# rcio_v2.net
KiCad netlist of a schematic drawn in EAGLE
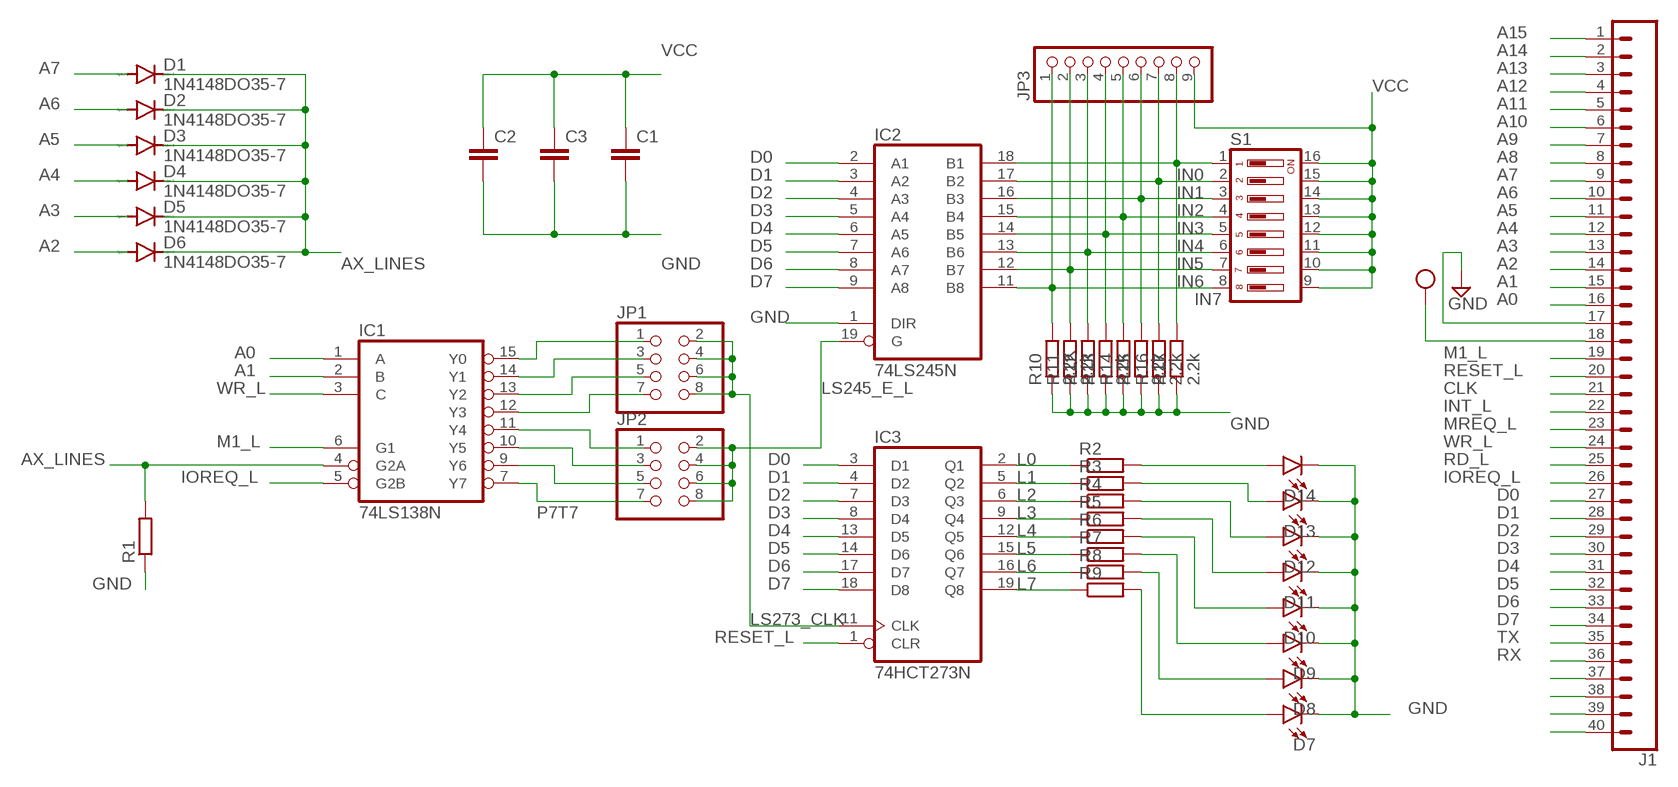
[diagram p0: schematic, sheet 1]

(export (version "E")
  (design (tool "Eeschema 10.0.6"))
  (components
    (comp (ref "C1")
      (value "C-EU050-025X075")
      (footprint "eagle-import:C050-025X075")
      (libsource (lib "eagle-import") (part "rcl_334_C-EU050-025X075"))
    )
    (comp (ref "C2")
      (value "C-EU050-025X075")
      (footprint "eagle-import:C050-025X075")
      (libsource (lib "eagle-import") (part "C-EU050-025X075"))
    )
    (comp (ref "C3")
      (value "C-EU050-025X075")
      (footprint "eagle-import:C050-025X075")
      (libsource (lib "eagle-import") (part "C-EU050-025X075"))
    )
    (comp (ref "D1")
      (value "1N4148DO35-7")
      (footprint "eagle-import:DO35-7")
      (libsource (lib "eagle-import") (part "1N4148DO35-7"))
    )
    (comp (ref "D2")
      (value "1N4148DO35-7")
      (footprint "eagle-import:DO35-7")
      (libsource (lib "eagle-import") (part "1N4148DO35-7"))
    )
    (comp (ref "D3")
      (value "1N4148DO35-7")
      (footprint "eagle-import:DO35-7")
      (libsource (lib "eagle-import") (part "1N4148DO35-7"))
    )
    (comp (ref "D4")
      (value "1N4148DO35-7")
      (footprint "eagle-import:DO35-7")
      (libsource (lib "eagle-import") (part "1N4148DO35-7"))
    )
    (comp (ref "D5")
      (value "1N4148DO35-7")
      (footprint "eagle-import:DO35-7")
      (libsource (lib "eagle-import") (part "1N4148DO35-7"))
    )
    (comp (ref "D6")
      (value "1N4148DO35-7")
      (footprint "eagle-import:DO35-7")
      (libsource (lib "eagle-import") (part "1N4148DO35-7"))
    )
    (comp (ref "D7")
      (value "LED3MM")
      (footprint "eagle-import:LED_3MM")
      (libsource (lib "eagle-import") (part "LED3MM"))
    )
    (comp (ref "D8")
      (value "LED3MM")
      (footprint "eagle-import:LED_3MM")
      (libsource (lib "eagle-import") (part "LED3MM"))
    )
    (comp (ref "D9")
      (value "LED3MM")
      (footprint "eagle-import:LED_3MM")
      (libsource (lib "eagle-import") (part "LED3MM"))
    )
    (comp (ref "D10")
      (value "LED3MM")
      (footprint "eagle-import:LED_3MM")
      (libsource (lib "eagle-import") (part "LED3MM"))
    )
    (comp (ref "D11")
      (value "LED3MM")
      (footprint "eagle-import:LED_3MM")
      (libsource (lib "eagle-import") (part "LED3MM"))
    )
    (comp (ref "D12")
      (value "LED3MM")
      (footprint "eagle-import:LED_3MM")
      (libsource (lib "eagle-import") (part "LED3MM"))
    )
    (comp (ref "D13")
      (value "LED3MM")
      (footprint "eagle-import:LED_3MM")
      (libsource (lib "eagle-import") (part "LED3MM"))
    )
    (comp (ref "D14")
      (value "LED3MM")
      (footprint "eagle-import:LED_3MM")
      (libsource (lib "eagle-import") (part "LED3MM"))
    )
    (comp (ref "IC1")
      (value "74LS138N")
      (footprint "eagle-import:DIL16")
      (libsource (lib "eagle-import") (part "74138NLS"))
    )
    (comp (ref "IC2")
      (value "74LS245N")
      (footprint "eagle-import:DIL20")
      (libsource (lib "eagle-import") (part "74245NLS"))
    )
    (comp (ref "IC3")
      (value "74HCT273N")
      (footprint "eagle-import:DIL20")
      (libsource (lib "eagle-import") (part "74273NHCT"))
    )
    (comp (ref "J1")
      (value "CONN_40OFFSET")
      (footprint "eagle-import:1X40_OFFSET")
      (libsource (lib "eagle-import") (part "CONN_40OFFSET"))
    )
    (comp (ref "JP1")
      (value "PINHD-2X4")
      (footprint "eagle-import:2X04")
      (libsource (lib "eagle-import") (part "PINHD-2X4"))
    )
    (comp (ref "JP2")
      (value "PINHD-2X4")
      (footprint "eagle-import:2X04")
      (libsource (lib "eagle-import") (part "PINHD-2X4"))
    )
    (comp (ref "JP3")
      (value "PINHD-1X9")
      (footprint "eagle-import:1X09")
      (libsource (lib "eagle-import") (part "PINHD-1X9"))
    )
    (comp (ref "R1")
      (value "R-EU_0204/7")
      (footprint "eagle-import:0204_7")
      (libsource (lib "eagle-import") (part "R-EU_0204/7"))
    )
    (comp (ref "R2")
      (value "R-EU_0204/7")
      (footprint "eagle-import:0204_7")
      (libsource (lib "eagle-import") (part "R-EU_0204/7"))
    )
    (comp (ref "R3")
      (value "R-EU_0204/7")
      (footprint "eagle-import:0204_7")
      (libsource (lib "eagle-import") (part "R-EU_0204/7"))
    )
    (comp (ref "R4")
      (value "R-EU_0204/7")
      (footprint "eagle-import:0204_7")
      (libsource (lib "eagle-import") (part "R-EU_0204/7"))
    )
    (comp (ref "R5")
      (value "R-EU_0204/7")
      (footprint "eagle-import:0204_7")
      (libsource (lib "eagle-import") (part "R-EU_0204/7"))
    )
    (comp (ref "R6")
      (value "R-EU_0204/7")
      (footprint "eagle-import:0204_7")
      (libsource (lib "eagle-import") (part "R-EU_0204/7"))
    )
    (comp (ref "R7")
      (value "R-EU_0204/7")
      (footprint "eagle-import:0204_7")
      (libsource (lib "eagle-import") (part "R-EU_0204/7"))
    )
    (comp (ref "R8")
      (value "R-EU_0204/7")
      (footprint "eagle-import:0204_7")
      (libsource (lib "eagle-import") (part "R-EU_0204/7"))
    )
    (comp (ref "R9")
      (value "R-EU_0204/7")
      (footprint "eagle-import:0204_7")
      (libsource (lib "eagle-import") (part "R-EU_0204/7"))
    )
    (comp (ref "R10")
      (value "2.2K")
      (footprint "eagle-import:0204_7")
      (libsource (lib "eagle-import") (part "R-EU_0204/7"))
    )
    (comp (ref "R11")
      (value "2.2k")
      (footprint "eagle-import:0204_7")
      (libsource (lib "eagle-import") (part "R-EU_0204/7"))
    )
    (comp (ref "R12")
      (value "R-EU_0204/7")
      (footprint "eagle-import:0204_7")
      (libsource (lib "eagle-import") (part "R-EU_0204/7"))
    )
    (comp (ref "R13")
      (value "2.2k")
      (footprint "eagle-import:0204_7")
      (libsource (lib "eagle-import") (part "R-EU_0204/7"))
    )
    (comp (ref "R14")
      (value "R-EU_0204/7")
      (footprint "eagle-import:0204_7")
      (libsource (lib "eagle-import") (part "R-EU_0204/7"))
    )
    (comp (ref "R15")
      (value "2.2k")
      (footprint "eagle-import:0204_7")
      (libsource (lib "eagle-import") (part "R-EU_0204/7"))
    )
    (comp (ref "R16")
      (value "2.2k")
      (footprint "eagle-import:0204_7")
      (libsource (lib "eagle-import") (part "R-EU_0204/7"))
    )
    (comp (ref "R17")
      (value "2.2k")
      (footprint "eagle-import:0204_7")
      (libsource (lib "eagle-import") (part "R-EU_0204/7"))
    )
    (comp (ref "S1")
      (value "DP08")
      (footprint "eagle-import:DP-08")
      (libsource (lib "eagle-import") (part "DP08"))
    )
  )
  (nets
    (net (code "1") (name "/A0") (class "Default")
      (node (ref "IC1") (pin "1") (pinfunction "A_1") (pintype "input"))
      (node (ref "J1") (pin "16") (pinfunction "16_16") (pintype "passive"))
    )
    (net (code "2") (name "/A1") (class "Default")
      (node (ref "IC1") (pin "2") (pinfunction "B_2") (pintype "input"))
      (node (ref "J1") (pin "15") (pinfunction "15_15") (pintype "passive"))
    )
    (net (code "3") (name "/A2") (class "Default")
      (node (ref "D6") (pin "A") (pinfunction "A_A") (pintype "passive"))
      (node (ref "J1") (pin "14") (pinfunction "14_14") (pintype "passive"))
    )
    (net (code "4") (name "/A3") (class "Default")
      (node (ref "D5") (pin "A") (pinfunction "A_A") (pintype "passive"))
      (node (ref "J1") (pin "13") (pinfunction "13_13") (pintype "passive"))
    )
    (net (code "5") (name "/A4") (class "Default")
      (node (ref "D4") (pin "A") (pinfunction "A_A") (pintype "passive"))
      (node (ref "J1") (pin "12") (pinfunction "12_12") (pintype "passive"))
    )
    (net (code "6") (name "/A5") (class "Default")
      (node (ref "D3") (pin "A") (pinfunction "A_A") (pintype "passive"))
      (node (ref "J1") (pin "11") (pinfunction "11_11") (pintype "passive"))
    )
    (net (code "7") (name "/A6") (class "Default")
      (node (ref "D2") (pin "A") (pinfunction "A_A") (pintype "passive"))
      (node (ref "J1") (pin "10") (pinfunction "10_10") (pintype "passive"))
    )
    (net (code "8") (name "/A7") (class "Default")
      (node (ref "D1") (pin "A") (pinfunction "A_A") (pintype "passive"))
      (node (ref "J1") (pin "9") (pinfunction "9_9") (pintype "passive"))
    )
    (net (code "9") (name "/A8") (class "Default")
      (node (ref "J1") (pin "8") (pinfunction "8_8") (pintype "passive"))
    )
    (net (code "10") (name "/A9") (class "Default")
      (node (ref "J1") (pin "7") (pinfunction "7_7") (pintype "passive"))
    )
    (net (code "11") (name "/A10") (class "Default")
      (node (ref "J1") (pin "6") (pinfunction "6_6") (pintype "passive"))
    )
    (net (code "12") (name "/A11") (class "Default")
      (node (ref "J1") (pin "5") (pinfunction "5_5") (pintype "passive"))
    )
    (net (code "13") (name "/A12") (class "Default")
      (node (ref "J1") (pin "4") (pinfunction "4_4") (pintype "passive"))
    )
    (net (code "14") (name "/A13") (class "Default")
      (node (ref "J1") (pin "3") (pinfunction "3_3") (pintype "passive"))
    )
    (net (code "15") (name "/A14") (class "Default")
      (node (ref "J1") (pin "2") (pinfunction "2_2") (pintype "passive"))
    )
    (net (code "16") (name "/A15") (class "Default")
      (node (ref "J1") (pin "1") (pinfunction "1_1") (pintype "passive"))
    )
    (net (code "17") (name "/AX_LINES") (class "Default")
      (node (ref "D1") (pin "C") (pinfunction "C_C") (pintype "passive"))
      (node (ref "D2") (pin "C") (pinfunction "C_C") (pintype "passive"))
      (node (ref "D3") (pin "C") (pinfunction "C_C") (pintype "passive"))
      (node (ref "D4") (pin "C") (pinfunction "C_C") (pintype "passive"))
      (node (ref "D5") (pin "C") (pinfunction "C_C") (pintype "passive"))
      (node (ref "D6") (pin "C") (pinfunction "C_C") (pintype "passive"))
      (node (ref "IC1") (pin "4") (pinfunction "G2A_4") (pintype "input"))
      (node (ref "R1") (pin "2") (pinfunction "2_2") (pintype "passive"))
    )
    (net (code "18") (name "/CLK") (class "Default")
      (node (ref "J1") (pin "21") (pinfunction "21_21") (pintype "passive"))
    )
    (net (code "19") (name "/D0") (class "Default")
      (node (ref "IC2") (pin "2") (pinfunction "A1_2") (pintype "bidirectional"))
      (node (ref "IC3") (pin "3") (pinfunction "D1_3") (pintype "input"))
      (node (ref "J1") (pin "27") (pinfunction "27_27") (pintype "passive"))
    )
    (net (code "20") (name "/D1") (class "Default")
      (node (ref "IC2") (pin "3") (pinfunction "A2_3") (pintype "bidirectional"))
      (node (ref "IC3") (pin "4") (pinfunction "D2_4") (pintype "input"))
      (node (ref "J1") (pin "28") (pinfunction "28_28") (pintype "passive"))
    )
    (net (code "21") (name "/D2") (class "Default")
      (node (ref "IC2") (pin "4") (pinfunction "A3_4") (pintype "bidirectional"))
      (node (ref "IC3") (pin "7") (pinfunction "D3_7") (pintype "input"))
      (node (ref "J1") (pin "29") (pinfunction "29_29") (pintype "passive"))
    )
    (net (code "22") (name "/D3") (class "Default")
      (node (ref "IC2") (pin "5") (pinfunction "A4_5") (pintype "bidirectional"))
      (node (ref "IC3") (pin "8") (pinfunction "D4_8") (pintype "input"))
      (node (ref "J1") (pin "30") (pinfunction "30_30") (pintype "passive"))
    )
    (net (code "23") (name "/D4") (class "Default")
      (node (ref "IC2") (pin "6") (pinfunction "A5_6") (pintype "bidirectional"))
      (node (ref "IC3") (pin "13") (pinfunction "D5_13") (pintype "input"))
      (node (ref "J1") (pin "31") (pinfunction "31_31") (pintype "passive"))
    )
    (net (code "24") (name "/D5") (class "Default")
      (node (ref "IC2") (pin "7") (pinfunction "A6_7") (pintype "bidirectional"))
      (node (ref "IC3") (pin "14") (pinfunction "D6_14") (pintype "input"))
      (node (ref "J1") (pin "32") (pinfunction "32_32") (pintype "passive"))
    )
    (net (code "25") (name "/D6") (class "Default")
      (node (ref "IC2") (pin "8") (pinfunction "A7_8") (pintype "bidirectional"))
      (node (ref "IC3") (pin "17") (pinfunction "D7_17") (pintype "input"))
      (node (ref "J1") (pin "33") (pinfunction "33_33") (pintype "passive"))
    )
    (net (code "26") (name "/D7") (class "Default")
      (node (ref "IC2") (pin "9") (pinfunction "A8_9") (pintype "bidirectional"))
      (node (ref "IC3") (pin "18") (pinfunction "D8_18") (pintype "input"))
      (node (ref "J1") (pin "34") (pinfunction "34_34") (pintype "passive"))
    )
    (net (code "27") (name "/IN0") (class "Default")
      (node (ref "IC2") (pin "18") (pinfunction "B1_18") (pintype "bidirectional"))
      (node (ref "JP3") (pin "8") (pinfunction "8_8") (pintype "passive"))
      (node (ref "R17") (pin "2") (pinfunction "2_2") (pintype "passive"))
      (node (ref "S1") (pin "1") (pinfunction "1_1") (pintype "passive"))
    )
    (net (code "28") (name "/IN1") (class "Default")
      (node (ref "IC2") (pin "17") (pinfunction "B2_17") (pintype "bidirectional"))
      (node (ref "JP3") (pin "7") (pinfunction "7_7") (pintype "passive"))
      (node (ref "R16") (pin "2") (pinfunction "2_2") (pintype "passive"))
      (node (ref "S1") (pin "2") (pinfunction "2_2") (pintype "passive"))
    )
    (net (code "29") (name "/IN2") (class "Default")
      (node (ref "IC2") (pin "16") (pinfunction "B3_16") (pintype "bidirectional"))
      (node (ref "JP3") (pin "6") (pinfunction "6_6") (pintype "passive"))
      (node (ref "R15") (pin "2") (pinfunction "2_2") (pintype "passive"))
      (node (ref "S1") (pin "3") (pinfunction "3_3") (pintype "passive"))
    )
    (net (code "30") (name "/IN3") (class "Default")
      (node (ref "IC2") (pin "15") (pinfunction "B4_15") (pintype "bidirectional"))
      (node (ref "JP3") (pin "5") (pinfunction "5_5") (pintype "passive"))
      (node (ref "R14") (pin "2") (pinfunction "2_2") (pintype "passive"))
      (node (ref "S1") (pin "4") (pinfunction "4_4") (pintype "passive"))
    )
    (net (code "31") (name "/IN4") (class "Default")
      (node (ref "IC2") (pin "14") (pinfunction "B5_14") (pintype "bidirectional"))
      (node (ref "JP3") (pin "4") (pinfunction "4_4") (pintype "passive"))
      (node (ref "R13") (pin "2") (pinfunction "2_2") (pintype "passive"))
      (node (ref "S1") (pin "5") (pinfunction "5_5") (pintype "passive"))
    )
    (net (code "32") (name "/IN5") (class "Default")
      (node (ref "IC2") (pin "13") (pinfunction "B6_13") (pintype "bidirectional"))
      (node (ref "JP3") (pin "3") (pinfunction "3_3") (pintype "passive"))
      (node (ref "R12") (pin "2") (pinfunction "2_2") (pintype "passive"))
      (node (ref "S1") (pin "6") (pinfunction "6_6") (pintype "passive"))
    )
    (net (code "33") (name "/IN6") (class "Default")
      (node (ref "IC2") (pin "12") (pinfunction "B7_12") (pintype "bidirectional"))
      (node (ref "JP3") (pin "2") (pinfunction "2_2") (pintype "passive"))
      (node (ref "R11") (pin "2") (pinfunction "2_2") (pintype "passive"))
      (node (ref "S1") (pin "7") (pinfunction "7_7") (pintype "passive"))
    )
    (net (code "34") (name "/IN7") (class "Default")
      (node (ref "IC2") (pin "11") (pinfunction "B8_11") (pintype "bidirectional"))
      (node (ref "JP3") (pin "1") (pinfunction "1_1") (pintype "passive"))
      (node (ref "R10") (pin "2") (pinfunction "2_2") (pintype "passive"))
      (node (ref "S1") (pin "8") (pinfunction "8_8") (pintype "passive"))
    )
    (net (code "35") (name "/INT_L") (class "Default")
      (node (ref "J1") (pin "22") (pinfunction "22_22") (pintype "passive"))
    )
    (net (code "36") (name "/IOREQ_L") (class "Default")
      (node (ref "IC1") (pin "5") (pinfunction "G2B_5") (pintype "input"))
      (node (ref "J1") (pin "26") (pinfunction "26_26") (pintype "passive"))
    )
    (net (code "37") (name "/L0") (class "Default")
      (node (ref "IC3") (pin "2") (pinfunction "Q1_2") (pintype "output"))
      (node (ref "R2") (pin "1") (pinfunction "1_1") (pintype "passive"))
    )
    (net (code "38") (name "/L1") (class "Default")
      (node (ref "IC3") (pin "5") (pinfunction "Q2_5") (pintype "output"))
      (node (ref "R3") (pin "1") (pinfunction "1_1") (pintype "passive"))
    )
    (net (code "39") (name "/L2") (class "Default")
      (node (ref "IC3") (pin "6") (pinfunction "Q3_6") (pintype "output"))
      (node (ref "R4") (pin "1") (pinfunction "1_1") (pintype "passive"))
    )
    (net (code "40") (name "/L3") (class "Default")
      (node (ref "IC3") (pin "9") (pinfunction "Q4_9") (pintype "output"))
      (node (ref "R5") (pin "1") (pinfunction "1_1") (pintype "passive"))
    )
    (net (code "41") (name "/L4") (class "Default")
      (node (ref "IC3") (pin "12") (pinfunction "Q5_12") (pintype "output"))
      (node (ref "R6") (pin "1") (pinfunction "1_1") (pintype "passive"))
    )
    (net (code "42") (name "/L5") (class "Default")
      (node (ref "IC3") (pin "15") (pinfunction "Q6_15") (pintype "output"))
      (node (ref "R7") (pin "1") (pinfunction "1_1") (pintype "passive"))
    )
    (net (code "43") (name "/L6") (class "Default")
      (node (ref "IC3") (pin "16") (pinfunction "Q7_16") (pintype "output"))
      (node (ref "R8") (pin "1") (pinfunction "1_1") (pintype "passive"))
    )
    (net (code "44") (name "/L7") (class "Default")
      (node (ref "IC3") (pin "19") (pinfunction "Q8_19") (pintype "output"))
      (node (ref "R9") (pin "1") (pinfunction "1_1") (pintype "passive"))
    )
    (net (code "45") (name "/LS245_E_L") (class "Default")
      (node (ref "IC2") (pin "19") (pinfunction "G_19") (pintype "input"))
      (node (ref "JP2") (pin "2") (pinfunction "2_2") (pintype "passive"))
      (node (ref "JP2") (pin "4") (pinfunction "4_4") (pintype "passive"))
      (node (ref "JP2") (pin "6") (pinfunction "6_6") (pintype "passive"))
      (node (ref "JP2") (pin "8") (pinfunction "8_8") (pintype "passive"))
    )
    (net (code "46") (name "/LS273_CLK") (class "Default")
      (node (ref "IC3") (pin "11") (pinfunction "CLK_11") (pintype "input"))
      (node (ref "JP1") (pin "2") (pinfunction "2_2") (pintype "passive"))
      (node (ref "JP1") (pin "4") (pinfunction "4_4") (pintype "passive"))
      (node (ref "JP1") (pin "6") (pinfunction "6_6") (pintype "passive"))
      (node (ref "JP1") (pin "8") (pinfunction "8_8") (pintype "passive"))
    )
    (net (code "47") (name "/M1_L") (class "Default")
      (node (ref "IC1") (pin "6") (pinfunction "G1_6") (pintype "input"))
      (node (ref "J1") (pin "19") (pinfunction "19_19") (pintype "passive"))
    )
    (net (code "48") (name "/MREQ_L") (class "Default")
      (node (ref "J1") (pin "23") (pinfunction "23_23") (pintype "passive"))
    )
    (net (code "49") (name "/P7T7") (class "Default")
      (node (ref "IC1") (pin "7") (pinfunction "Y7_7") (pintype "output"))
      (node (ref "JP2") (pin "7") (pinfunction "7_7") (pintype "passive"))
    )
    (net (code "50") (name "/RD_L") (class "Default")
      (node (ref "J1") (pin "25") (pinfunction "25_25") (pintype "passive"))
    )
    (net (code "51") (name "/RESET_L") (class "Default")
      (node (ref "IC3") (pin "1") (pinfunction "CLR_1") (pintype "input"))
      (node (ref "J1") (pin "20") (pinfunction "20_20") (pintype "passive"))
    )
    (net (code "52") (name "/RX") (class "Default")
      (node (ref "J1") (pin "36") (pinfunction "36_36") (pintype "passive"))
    )
    (net (code "53") (name "/TX") (class "Default")
      (node (ref "J1") (pin "35") (pinfunction "35_35") (pintype "passive"))
    )
    (net (code "54") (name "/WR_L") (class "Default")
      (node (ref "IC1") (pin "3") (pinfunction "C_3") (pintype "input"))
      (node (ref "J1") (pin "24") (pinfunction "24_24") (pintype "passive"))
    )
    (net (code "55") (name "GND") (class "Default")
      (node (ref "C1") (pin "2") (pinfunction "2_2") (pintype "passive"))
      (node (ref "C2") (pin "2") (pinfunction "2_2") (pintype "passive"))
      (node (ref "C3") (pin "2") (pinfunction "2_2") (pintype "passive"))
      (node (ref "D10") (pin "K") (pinfunction "C_K") (pintype "passive"))
      (node (ref "D11") (pin "K") (pinfunction "C_K") (pintype "passive"))
      (node (ref "D12") (pin "K") (pinfunction "C_K") (pintype "passive"))
      (node (ref "D13") (pin "K") (pinfunction "C_K") (pintype "passive"))
      (node (ref "D14") (pin "K") (pinfunction "C_K") (pintype "passive"))
      (node (ref "D7") (pin "K") (pinfunction "C_K") (pintype "passive"))
      (node (ref "D8") (pin "K") (pinfunction "C_K") (pintype "passive"))
      (node (ref "D9") (pin "K") (pinfunction "C_K") (pintype "passive"))
      (node (ref "IC2") (pin "1") (pinfunction "DIR_1") (pintype "input"))
      (node (ref "J1") (pin "17") (pinfunction "17_17") (pintype "passive"))
      (node (ref "R1") (pin "1") (pinfunction "1_1") (pintype "passive"))
      (node (ref "R10") (pin "1") (pinfunction "1_1") (pintype "passive"))
      (node (ref "R11") (pin "1") (pinfunction "1_1") (pintype "passive"))
      (node (ref "R12") (pin "1") (pinfunction "1_1") (pintype "passive"))
      (node (ref "R13") (pin "1") (pinfunction "1_1") (pintype "passive"))
      (node (ref "R14") (pin "1") (pinfunction "1_1") (pintype "passive"))
      (node (ref "R15") (pin "1") (pinfunction "1_1") (pintype "passive"))
      (node (ref "R16") (pin "1") (pinfunction "1_1") (pintype "passive"))
      (node (ref "R17") (pin "1") (pinfunction "1_1") (pintype "passive"))
    )
    (net (code "56") (name "Net-(D7-PadA)") (class "Default")
      (node (ref "D7") (pin "A") (pinfunction "A_A") (pintype "passive"))
      (node (ref "R9") (pin "2") (pinfunction "2_2") (pintype "passive"))
    )
    (net (code "57") (name "Net-(D8-PadA)") (class "Default")
      (node (ref "D8") (pin "A") (pinfunction "A_A") (pintype "passive"))
      (node (ref "R8") (pin "2") (pinfunction "2_2") (pintype "passive"))
    )
    (net (code "58") (name "Net-(D9-PadA)") (class "Default")
      (node (ref "D9") (pin "A") (pinfunction "A_A") (pintype "passive"))
      (node (ref "R7") (pin "2") (pinfunction "2_2") (pintype "passive"))
    )
    (net (code "59") (name "Net-(D10-PadA)") (class "Default")
      (node (ref "D10") (pin "A") (pinfunction "A_A") (pintype "passive"))
      (node (ref "R6") (pin "2") (pinfunction "2_2") (pintype "passive"))
    )
    (net (code "60") (name "Net-(D11-PadA)") (class "Default")
      (node (ref "D11") (pin "A") (pinfunction "A_A") (pintype "passive"))
      (node (ref "R5") (pin "2") (pinfunction "2_2") (pintype "passive"))
    )
    (net (code "61") (name "Net-(D12-PadA)") (class "Default")
      (node (ref "D12") (pin "A") (pinfunction "A_A") (pintype "passive"))
      (node (ref "R4") (pin "2") (pinfunction "2_2") (pintype "passive"))
    )
    (net (code "62") (name "Net-(D13-PadA)") (class "Default")
      (node (ref "D13") (pin "A") (pinfunction "A_A") (pintype "passive"))
      (node (ref "R3") (pin "2") (pinfunction "2_2") (pintype "passive"))
    )
    (net (code "63") (name "Net-(D14-PadA)") (class "Default")
      (node (ref "D14") (pin "A") (pinfunction "A_A") (pintype "passive"))
      (node (ref "R2") (pin "2") (pinfunction "2_2") (pintype "passive"))
    )
    (net (code "64") (name "Net-(IC1A-Y0)") (class "Default")
      (node (ref "IC1") (pin "15") (pinfunction "Y0_15") (pintype "output"))
      (node (ref "JP1") (pin "1") (pinfunction "1_1") (pintype "passive"))
    )
    (net (code "65") (name "Net-(IC1A-Y1)") (class "Default")
      (node (ref "IC1") (pin "14") (pinfunction "Y1_14") (pintype "output"))
      (node (ref "JP1") (pin "3") (pinfunction "3_3") (pintype "passive"))
    )
    (net (code "66") (name "Net-(IC1A-Y2)") (class "Default")
      (node (ref "IC1") (pin "13") (pinfunction "Y2_13") (pintype "output"))
      (node (ref "JP1") (pin "5") (pinfunction "5_5") (pintype "passive"))
    )
    (net (code "67") (name "Net-(IC1A-Y3)") (class "Default")
      (node (ref "IC1") (pin "12") (pinfunction "Y3_12") (pintype "output"))
      (node (ref "JP1") (pin "7") (pinfunction "7_7") (pintype "passive"))
    )
    (net (code "68") (name "Net-(IC1A-Y4)") (class "Default")
      (node (ref "IC1") (pin "11") (pinfunction "Y4_11") (pintype "output"))
      (node (ref "JP2") (pin "1") (pinfunction "1_1") (pintype "passive"))
    )
    (net (code "69") (name "Net-(IC1A-Y5)") (class "Default")
      (node (ref "IC1") (pin "10") (pinfunction "Y5_10") (pintype "output"))
      (node (ref "JP2") (pin "3") (pinfunction "3_3") (pintype "passive"))
    )
    (net (code "70") (name "Net-(IC1A-Y6)") (class "Default")
      (node (ref "IC1") (pin "9") (pinfunction "Y6_9") (pintype "output"))
      (node (ref "JP2") (pin "5") (pinfunction "5_5") (pintype "passive"))
    )
    (net (code "71") (name "VCC") (class "Default")
      (node (ref "C1") (pin "1") (pinfunction "1_1") (pintype "passive"))
      (node (ref "C2") (pin "1") (pinfunction "1_1") (pintype "passive"))
      (node (ref "C3") (pin "1") (pinfunction "1_1") (pintype "passive"))
      (node (ref "J1") (pin "18") (pinfunction "18_18") (pintype "passive"))
      (node (ref "JP3") (pin "9") (pinfunction "9_9") (pintype "passive"))
      (node (ref "S1") (pin "10") (pinfunction "10_10") (pintype "passive"))
      (node (ref "S1") (pin "11") (pinfunction "11_11") (pintype "passive"))
      (node (ref "S1") (pin "12") (pinfunction "12_12") (pintype "passive"))
      (node (ref "S1") (pin "13") (pinfunction "13_13") (pintype "passive"))
      (node (ref "S1") (pin "14") (pinfunction "14_14") (pintype "passive"))
      (node (ref "S1") (pin "15") (pinfunction "15_15") (pintype "passive"))
      (node (ref "S1") (pin "16") (pinfunction "16_16") (pintype "passive"))
      (node (ref "S1") (pin "9") (pinfunction "9_9") (pintype "passive"))
    )
    (net (code "72") (name "unconnected-(J1-Pad37)") (class "Default")
      (node (ref "J1") (pin "37") (pinfunction "37_37") (pintype "passive"))
    )
    (net (code "73") (name "unconnected-(J1-Pad38)") (class "Default")
      (node (ref "J1") (pin "38") (pinfunction "38_38") (pintype "passive"))
    )
    (net (code "74") (name "unconnected-(J1-Pad39)") (class "Default")
      (node (ref "J1") (pin "39") (pinfunction "39_39") (pintype "passive"))
    )
    (net (code "75") (name "unconnected-(J1-Pad40)") (class "Default")
      (node (ref "J1") (pin "40") (pinfunction "40_40") (pintype "passive"))
    )
  )
)
